# CAN.net
KiCad netlist of a schematic drawn in Altium Designer
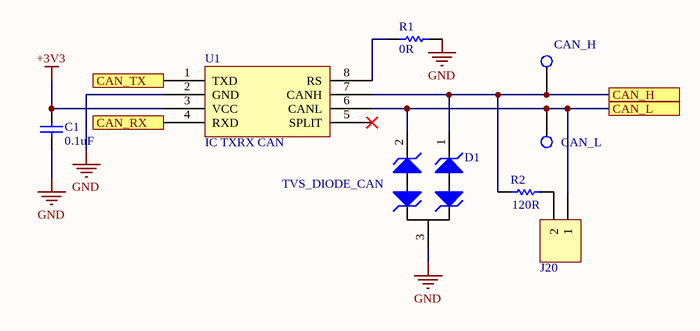
[diagram p0: CAN.SchDoc]

(export (version "E")
  (design (tool "Eeschema 10.0.6"))
  (components
    (comp (ref "C1")
      (value "0.1uF")
      (footprint "CAPC0603(1608)55_N")
      (description "CAP CER 0.1UF 16V X7R 0603")
      (fields (field (name "MANUFACTURER") "Yageo") (field (name "MPN") "CC0603KRX7R7BB104"))
      (libsource (lib "UWRT_Schematic_Library_2019") (part "CAP_0.1uF_16V_0603"))
    )
    (comp (ref "D1")
      (value "TVS_DIODE_CAN")
      (footprint "UWRT_Footprint_Library_2019:TVS_DIODE_CAN")
      (description "TVS DIODE 24V 41V SOT323-3")
      (fields (field (name "MANUFACTURER") "Nexperia USA Inc.") (field (name "MPN") "PESD2CAN,215"))
      (libsource (lib "UWRT_Schematic_Library_2019") (part "TVS_DIODE_CAN"))
    )
    (comp (ref "J20")
      (value "JUMPER")
      (footprint "HDR1X2")
      (description "HEADER 2X1")
      (libsource (lib "UWRT_Schematic_Library_2019") (part "JUMPER_2"))
    )
    (comp (ref "R1")
      (value "0R")
      (footprint "RESC0603(1608)_N")
      (description "RES SMD 0 OHM JUMPER 1/10W 0603")
      (fields (field (name "MANUFACTURER") "Yageo") (field (name "MPN") "RC0603JR-070RL"))
      (libsource (lib "UWRT_Schematic_Library_2019") (part "RES_0R_0603"))
    )
    (comp (ref "R2")
      (value "120R")
      (footprint "RESC0603(1608)_N")
      (description "RES SMD 120 OHM 5% 1/10W 0603")
      (fields (field (name "MANUFACTURER") "Yageo") (field (name "TOLERANCE") "5%"))
      (libsource (lib "UWRT_Schematic_Library_2019") (part "RES_120R_0603"))
    )
    (comp (ref "TP1")
      (value "CAN_H")
      (footprint "TESTPOINT_LOOP")
      (description "PC TEST POINT MINIATURE WHITE")
      (fields
        (field (name "DIGIKEY PART NUMBER") "36-5002-ND")
        (field (name "MANUFACTURER") "Keystone Electronics")
      )
      (libsource (lib "UWRT_Schematic_Library_2019") (part "TESTPOINT_LOOP"))
    )
    (comp (ref "TP2")
      (value "CAN_L")
      (footprint "TESTPOINT_LOOP")
      (description "PC TEST POINT MINIATURE WHITE")
      (fields
        (field (name "DIGIKEY PART NUMBER") "36-5002-ND")
        (field (name "MANUFACTURER") "Keystone Electronics")
      )
      (libsource (lib "UWRT_Schematic_Library_2019") (part "TESTPOINT_LOOP"))
    )
    (comp (ref "U1")
      (value "IC TXRX CAN")
      (footprint "LT-S8_N")
      (description "IC TXRX CAN 4MBPS 8SO")
      (fields (field (name "MANUFACTURER") "Linear Technologies") (field (name "MPN") "LTC2875IS8#PBF"))
      (libsource (lib "UWRT_Schematic_Library_2019") (part "LTC2875"))
    )
  )
  (nets
    (net (code "1") (name "+3V3") (class "Default")
      (node (ref "C1") (pin "2") (pinfunction "2_2") (pintype "passive"))
      (node (ref "U1") (pin "3") (pinfunction "VCC_3") (pintype "passive"))
    )
    (net (code "2") (name "/CAN_H") (class "Default")
      (node (ref "D1") (pin "1") (pinfunction "1_1") (pintype "passive"))
      (node (ref "R2") (pin "1") (pinfunction "1_1") (pintype "passive"))
      (node (ref "TP1") (pin "1") (pintype "passive"))
      (node (ref "U1") (pin "7") (pinfunction "CANH_7") (pintype "passive"))
    )
    (net (code "3") (name "/CAN_L") (class "Default")
      (node (ref "D1") (pin "2") (pinfunction "2_2") (pintype "passive"))
      (node (ref "J20") (pin "1") (pinfunction "1_1") (pintype "passive"))
      (node (ref "TP2") (pin "1") (pintype "passive"))
      (node (ref "U1") (pin "6") (pinfunction "CANL_6") (pintype "passive"))
    )
    (net (code "4") (name "/CAN_RX") (class "Default")
      (node (ref "U1") (pin "4") (pinfunction "RXD_4") (pintype "passive"))
    )
    (net (code "5") (name "/CAN_TX") (class "Default")
      (node (ref "U1") (pin "1") (pinfunction "TXD_1") (pintype "passive"))
    )
    (net (code "6") (name "GND") (class "Default")
      (node (ref "C1") (pin "1") (pinfunction "1_1") (pintype "passive"))
      (node (ref "D1") (pin "3") (pinfunction "3_3") (pintype "passive"))
      (node (ref "R1") (pin "2") (pinfunction "2_2") (pintype "passive"))
      (node (ref "U1") (pin "2") (pinfunction "GND_2") (pintype "passive"))
    )
    (net (code "7") (name "Net-(J20-Pad2)") (class "Default")
      (node (ref "J20") (pin "2") (pinfunction "2_2") (pintype "passive"))
      (node (ref "R2") (pin "2") (pinfunction "2_2") (pintype "passive"))
    )
    (net (code "8") (name "Net-(U1-RS)") (class "Default")
      (node (ref "R1") (pin "1") (pinfunction "1_1") (pintype "passive"))
      (node (ref "U1") (pin "8") (pinfunction "RS_8") (pintype "passive"))
    )
    (net (code "9") (name "unconnected-(U1-SPLIT-Pad5)") (class "Default")
      (node (ref "U1") (pin "5") (pinfunction "SPLIT_5") (pintype "passive+no_connect"))
    )
  )
)
